# ELCD.net
KiCad netlist of a schematic drawn in Altium Designer
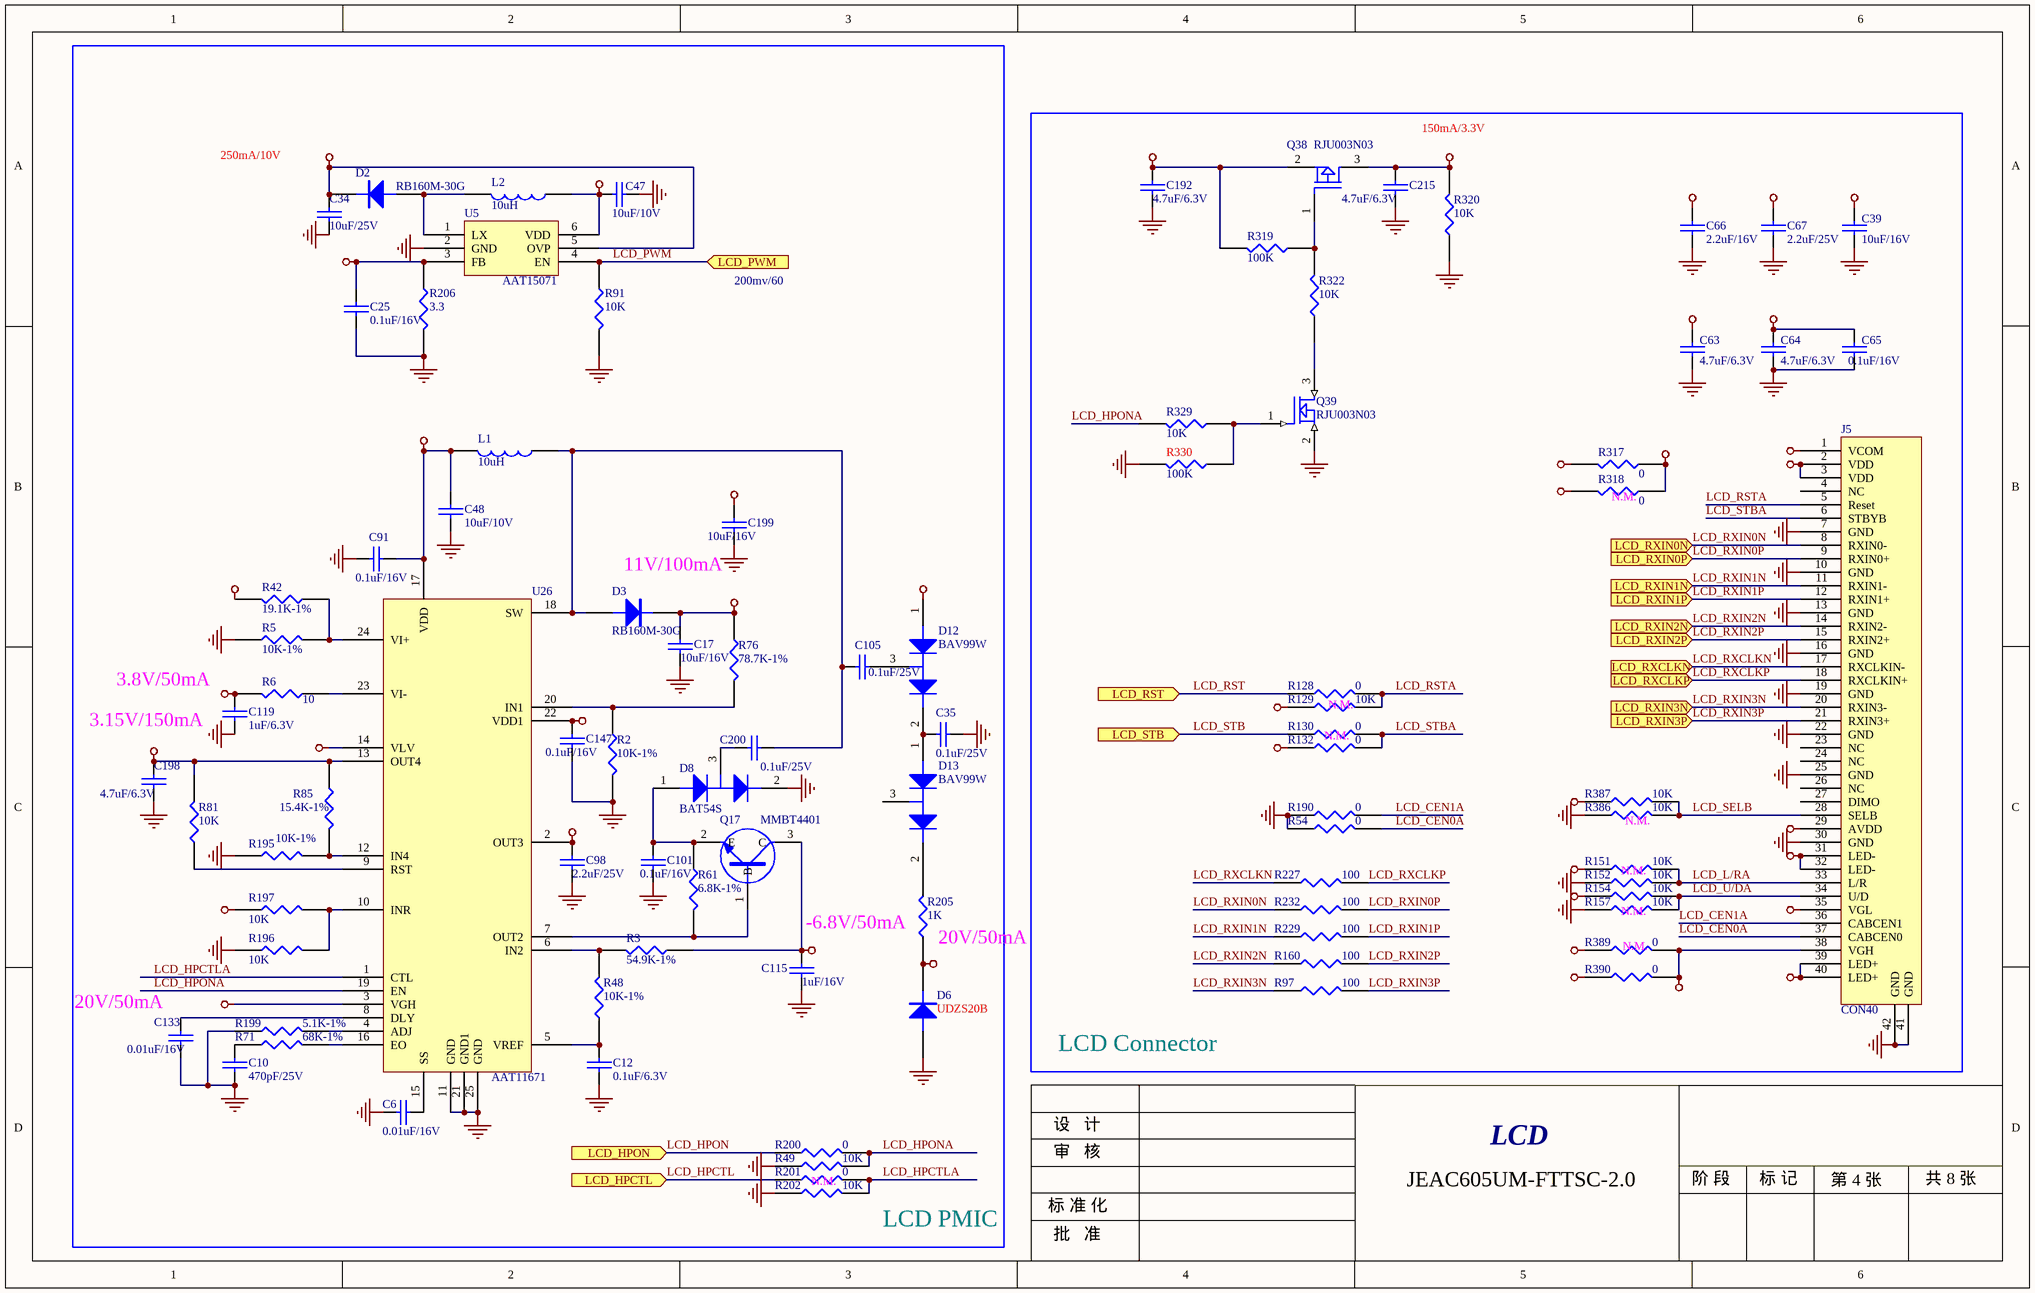
[diagram p0: ELCD.schdoc]

(export (version "E")
  (design (tool "Eeschema 10.0.6"))
  (components
    (comp (ref "C6")
      (value "0.01uF/16V")
      (footprint "C0402")
      (description "Capacitor")
      (libsource (lib "*") (part "CAP"))
    )
    (comp (ref "C10")
      (value "470pF/25V")
      (footprint "C0402")
      (description "Capacitor")
      (libsource (lib "*") (part "CAP"))
    )
    (comp (ref "C12")
      (value "0.1uF/6.3V")
      (footprint "C0402")
      (description "Capacitor")
      (libsource (lib "*") (part "CAP"))
    )
    (comp (ref "C17")
      (value "10uF/16V")
      (footprint "C1206")
      (description "Capacitor")
      (libsource (lib "*") (part "CAP"))
    )
    (comp (ref "C25")
      (value "0.1uF/16V")
      (footprint "C0402")
      (description "Capacitor")
      (libsource (lib "*") (part "CAP"))
    )
    (comp (ref "C34")
      (value "10uF/25V")
      (footprint "C1206")
      (description "Capacitor")
      (libsource (lib "*") (part "CAP"))
    )
    (comp (ref "C35")
      (value "0.1uF/25V")
      (footprint "C0603")
      (description "Capacitor")
      (libsource (lib "*") (part "CAP"))
    )
    (comp (ref "C39")
      (value "10uF/16V")
      (footprint "C1206")
      (description "Capacitor")
      (libsource (lib "*") (part "CAP"))
    )
    (comp (ref "C47")
      (value "10uF/10V")
      (footprint "C0805")
      (description "Capacitor")
      (libsource (lib "*") (part "CAP"))
    )
    (comp (ref "C48")
      (value "10uF/10V")
      (footprint "C0805")
      (description "Capacitor")
      (libsource (lib "*") (part "CAP"))
    )
    (comp (ref "C63")
      (value "4.7uF/6.3V")
      (footprint "C0603")
      (description "Capacitor")
      (libsource (lib "*") (part "CAP"))
    )
    (comp (ref "C64")
      (value "4.7uF/6.3V")
      (footprint "C0603")
      (description "Capacitor")
      (libsource (lib "*") (part "CAP"))
    )
    (comp (ref "C65")
      (value "0.1uF/16V")
      (footprint "C0402")
      (description "Capacitor")
      (libsource (lib "*") (part "CAP"))
    )
    (comp (ref "C66")
      (value "2.2uF/16V")
      (footprint "C0805")
      (description "Capacitor")
      (libsource (lib "*") (part "CAP"))
    )
    (comp (ref "C67")
      (value "2.2uF/25V")
      (footprint "C0805")
      (description "Capacitor")
      (libsource (lib "*") (part "CAP"))
    )
    (comp (ref "C91")
      (value "0.1uF/16V")
      (footprint "C0402")
      (description "Capacitor")
      (libsource (lib "*") (part "CAP"))
    )
    (comp (ref "C98")
      (value "0.1uF/16V")
      (footprint "C0805")
      (description "Capacitor")
      (libsource (lib "*") (part "CAP"))
    )
    (comp (ref "C101")
      (value "2.2uF/25V")
      (footprint "C0402")
      (description "Capacitor")
      (libsource (lib "*") (part "CAP"))
    )
    (comp (ref "C105")
      (value "0.1uF/25V")
      (footprint "C0603")
      (description "Capacitor")
      (libsource (lib "*") (part "CAP"))
    )
    (comp (ref "C115")
      (value "1uF/16V")
      (footprint "C0603")
      (description "Capacitor")
      (libsource (lib "*") (part "CAP"))
    )
    (comp (ref "C119")
      (value "1uF/6.3V")
      (footprint "C0402")
      (description "Capacitor")
      (libsource (lib "*") (part "CAP"))
    )
    (comp (ref "C133")
      (value "0.01uF/16V")
      (footprint "C0402")
      (description "Capacitor")
      (libsource (lib "*") (part "CAP"))
    )
    (comp (ref "C147")
      (value "0.1uF/16V")
      (footprint "C0402")
      (description "Capacitor")
      (libsource (lib "*") (part "CAP"))
    )
    (comp (ref "C192")
      (value "4.7uF/6.3V")
      (footprint "C0603")
      (description "Capacitor")
      (libsource (lib "*") (part "CAP"))
    )
    (comp (ref "C198")
      (value "4.7uF/6.3V")
      (footprint "C0603")
      (description "Capacitor")
      (libsource (lib "*") (part "CAP"))
    )
    (comp (ref "C199")
      (value "10uF/16V")
      (footprint "C1206")
      (description "Capacitor")
      (libsource (lib "*") (part "CAP"))
    )
    (comp (ref "C200")
      (value "0.1uF/25V")
      (footprint "C0603")
      (description "Capacitor")
      (libsource (lib "*") (part "CAP"))
    )
    (comp (ref "C215")
      (value "4.7uF/6.3V")
      (footprint "C0603")
      (description "Capacitor")
      (libsource (lib "*") (part "CAP"))
    )
    (comp (ref "D2") (value "RB160M-30G") (footprint "SOD-123") (libsource (lib "*") (part "DIODE")))
    (comp (ref "D3") (value "RB160M-30G") (footprint "SOD-123") (libsource (lib "*") (part "DIODE")))
    (comp (ref "D6") (value "UDZS20B") (footprint "UDZS24B") (libsource (lib "*") (part "DIODE")))
    (comp (ref "D8") (value "BAT54S") (footprint "SOT-23") (libsource (lib "DXP-SCHLIB") (part "MBRS1100")))
    (comp (ref "D12") (value "BAV99W") (footprint "SOT-23") (libsource (lib "") (part "MBRS1100_1")))
    (comp (ref "D13") (value "BAV99W") (footprint "SOT-23") (libsource (lib "") (part "MBRS1100_1")))
    (comp (ref "J5") (value "CON40") (footprint "j-con-40-0_5f") (libsource (lib "IMX53") (part "CON40")))
    (comp (ref "L1") (value "10uH") (footprint "l-2-EIA1008") (libsource (lib "*") (part "INDUCTOR1")))
    (comp (ref "L2") (value "10uH") (footprint "l-2-EIA1008") (libsource (lib "*") (part "INDUCTOR1")))
    (comp (ref "Q17")
      (value "MMBT4401")
      (footprint "SOT-23-NPN")
      (description "NPN Transistor")
      (libsource (lib "*") (part "NPN"))
    )
    (comp (ref "Q38") (value "RJU003N03") (footprint "SOT-23") (libsource (lib "*") (part "SI1021")))
    (comp (ref "Q39") (value "RJU003N03") (footprint "SOT-23-NPN") (libsource (lib "*") (part "MOSFET N")))
    (comp (ref "R2") (value "10K-1%") (footprint "R0402") (libsource (lib "*") (part "RES1")))
    (comp (ref "R3") (value "54.9K-1%") (footprint "R0402") (libsource (lib "*") (part "RES1")))
    (comp (ref "R5") (value "10K-1%") (footprint "R0402") (libsource (lib "*") (part "RES1")))
    (comp (ref "R6") (value "10") (footprint "R0402") (libsource (lib "*") (part "RES1")))
    (comp (ref "R42") (value "19.1K-1%") (footprint "R0402") (libsource (lib "*") (part "RES1")))
    (comp (ref "R48") (value "10K-1%") (footprint "R0402") (libsource (lib "*") (part "RES1")))
    (comp (ref "R49") (value "10K") (footprint "R0402") (libsource (lib "*") (part "RES1")))
    (comp (ref "R54") (value "0") (footprint "R0402") (libsource (lib "*") (part "RES1")))
    (comp (ref "R61") (value "6.8K-1%") (footprint "R0402") (libsource (lib "*") (part "RES1")))
    (comp (ref "R71") (value "68K-1%") (footprint "R0402") (libsource (lib "*") (part "RES1")))
    (comp (ref "R76") (value "78.7K-1%") (footprint "R0402") (libsource (lib "*") (part "RES1")))
    (comp (ref "R81") (value "10K") (footprint "R0402") (libsource (lib "*") (part "RES1")))
    (comp (ref "R85") (value "15.4K-1%") (footprint "R0402") (libsource (lib "*") (part "RES1")))
    (comp (ref "R91") (value "10K") (footprint "R0402") (libsource (lib "*") (part "RES1")))
    (comp (ref "R97") (value "100") (footprint "R0402") (libsource (lib "*") (part "RES1")))
    (comp (ref "R128") (value "0") (footprint "R0402") (libsource (lib "*") (part "RES1")))
    (comp (ref "R129") (value "10K") (footprint "R0402") (libsource (lib "*") (part "RES1")))
    (comp (ref "R130") (value "0") (footprint "R0402") (libsource (lib "*") (part "RES1")))
    (comp (ref "R132") (value "0") (footprint "R0402") (libsource (lib "*") (part "RES1")))
    (comp (ref "R151") (value "10K") (footprint "R0402") (libsource (lib "*") (part "RES1")))
    (comp (ref "R152") (value "10K") (footprint "R0402") (libsource (lib "*") (part "RES1")))
    (comp (ref "R154") (value "10K") (footprint "R0402") (libsource (lib "*") (part "RES1")))
    (comp (ref "R157") (value "10K") (footprint "R0402") (libsource (lib "*") (part "RES1")))
    (comp (ref "R160") (value "100") (footprint "R0402") (libsource (lib "*") (part "RES1")))
    (comp (ref "R190") (value "0") (footprint "R0402") (libsource (lib "*") (part "RES1")))
    (comp (ref "R195") (value "10K-1%") (footprint "R0402") (libsource (lib "*") (part "RES1")))
    (comp (ref "R196") (value "10K") (footprint "R0402") (libsource (lib "*") (part "RES1")))
    (comp (ref "R197") (value "10K") (footprint "R0402") (libsource (lib "*") (part "RES1")))
    (comp (ref "R199") (value "5.1K-1%") (footprint "R0402") (libsource (lib "*") (part "RES1")))
    (comp (ref "R200") (value "0") (footprint "R0402") (libsource (lib "*") (part "RES1")))
    (comp (ref "R201") (value "0") (footprint "R0402") (libsource (lib "*") (part "RES1")))
    (comp (ref "R202") (value "10K") (footprint "R0402") (libsource (lib "*") (part "RES1")))
    (comp (ref "R205") (value "1K") (footprint "R0603") (libsource (lib "*") (part "RES1")))
    (comp (ref "R206") (value "3.3") (footprint "R0603") (libsource (lib "*") (part "RES1")))
    (comp (ref "R227") (value "100") (footprint "R0402") (libsource (lib "*") (part "RES1")))
    (comp (ref "R229") (value "100") (footprint "R0402") (libsource (lib "*") (part "RES1")))
    (comp (ref "R232") (value "100") (footprint "R0402") (libsource (lib "*") (part "RES1")))
    (comp (ref "R317") (value "0") (footprint "R0402") (libsource (lib "*") (part "RES1")))
    (comp (ref "R318") (value "0") (footprint "R0402") (libsource (lib "*") (part "RES1")))
    (comp (ref "R319") (value "100K") (footprint "R0402") (libsource (lib "*") (part "RES1")))
    (comp (ref "R320") (value "10K") (footprint "R0402") (libsource (lib "*") (part "RES1")))
    (comp (ref "R322") (value "10K") (footprint "R0402") (libsource (lib "*") (part "RES1")))
    (comp (ref "R329") (value "10K") (footprint "R0402") (libsource (lib "*") (part "RES1")))
    (comp (ref "R330") (value "100K") (footprint "R0402") (libsource (lib "*") (part "RES1")))
    (comp (ref "R386") (value "10K") (footprint "R0402") (libsource (lib "*") (part "RES1")))
    (comp (ref "R387") (value "10K") (footprint "R0402") (libsource (lib "*") (part "RES1")))
    (comp (ref "R389") (value "0") (footprint "R0402") (libsource (lib "*") (part "RES1")))
    (comp (ref "R390") (value "0") (footprint "R0402") (libsource (lib "*") (part "RES1")))
    (comp (ref "U5") (value "AAT15071") (footprint "SOT23-6-0_95") (libsource (lib "*") (part "AAT15071")))
    (comp (ref "U26")
      (value "AAT11671")
      (footprint "U-QFN-24-0_5")
      (libsource (lib "Schlib1") (part "AAT11671"))
    )
  )
  (nets
    (net (code "1") (name "/LCD_CEN0A") (class "Default")
      (node (ref "J5") (pin "37") (pinfunction "CABCEN0_37") (pintype "passive"))
      (node (ref "R54") (pin "2") (pinfunction "2_2") (pintype "passive"))
    )
    (net (code "2") (name "/LCD_CEN1A") (class "Default")
      (node (ref "J5") (pin "36") (pinfunction "CABCEN1_36") (pintype "passive"))
      (node (ref "R190") (pin "2") (pinfunction "2_2") (pintype "passive"))
    )
    (net (code "3") (name "/LCD_HPCTL") (class "Default")
      (node (ref "R201") (pin "1") (pinfunction "1_1") (pintype "passive"))
    )
    (net (code "4") (name "/LCD_HPCTLA") (class "Default")
      (node (ref "R201") (pin "2") (pinfunction "2_2") (pintype "passive"))
      (node (ref "R202") (pin "2") (pinfunction "2_2") (pintype "passive"))
      (node (ref "U26") (pin "1") (pinfunction "CTL_1") (pintype "passive"))
    )
    (net (code "5") (name "/LCD_HPON") (class "Default")
      (node (ref "R200") (pin "1") (pinfunction "1_1") (pintype "passive"))
    )
    (net (code "6") (name "/LCD_HPONA") (class "Default")
      (node (ref "R200") (pin "2") (pinfunction "2_2") (pintype "passive"))
      (node (ref "R329") (pin "2") (pinfunction "2_2") (pintype "passive"))
      (node (ref "R49") (pin "2") (pinfunction "2_2") (pintype "passive"))
      (node (ref "U26") (pin "19") (pinfunction "EN_19") (pintype "passive"))
    )
    (net (code "7") (name "/LCD_L{slash}RA") (class "Default")
      (node (ref "J5") (pin "33") (pinfunction "L/R_33") (pintype "passive"))
      (node (ref "R151") (pin "2") (pinfunction "2_2") (pintype "passive"))
      (node (ref "R152") (pin "2") (pinfunction "2_2") (pintype "passive"))
    )
    (net (code "8") (name "/LCD_PWM") (class "Default")
      (node (ref "R91") (pin "1") (pinfunction "1_1") (pintype "passive"))
      (node (ref "U5") (pin "4") (pinfunction "EN_4") (pintype "passive"))
    )
    (net (code "9") (name "/LCD_RST") (class "Default")
      (node (ref "R128") (pin "1") (pinfunction "1_1") (pintype "passive"))
    )
    (net (code "10") (name "/LCD_RSTA") (class "Default")
      (node (ref "J5") (pin "5") (pinfunction "Reset_5") (pintype "passive"))
      (node (ref "R128") (pin "2") (pinfunction "2_2") (pintype "passive"))
      (node (ref "R129") (pin "2") (pinfunction "2_2") (pintype "passive"))
    )
    (net (code "11") (name "/LCD_RXCLKN") (class "Default")
      (node (ref "J5") (pin "17") (pinfunction "RXCLKIN-_17") (pintype "passive"))
      (node (ref "R227") (pin "1") (pinfunction "1_1") (pintype "passive"))
    )
    (net (code "12") (name "/LCD_RXCLKP") (class "Default")
      (node (ref "J5") (pin "18") (pinfunction "RXCLKIN+_18") (pintype "passive"))
      (node (ref "R227") (pin "2") (pinfunction "2_2") (pintype "passive"))
    )
    (net (code "13") (name "/LCD_RXIN0N") (class "Default")
      (node (ref "J5") (pin "8") (pinfunction "RXIN0-_8") (pintype "passive"))
      (node (ref "R232") (pin "1") (pinfunction "1_1") (pintype "passive"))
    )
    (net (code "14") (name "/LCD_RXIN0P") (class "Default")
      (node (ref "J5") (pin "9") (pinfunction "RXIN0+_9") (pintype "passive"))
      (node (ref "R232") (pin "2") (pinfunction "2_2") (pintype "passive"))
    )
    (net (code "15") (name "/LCD_RXIN1N") (class "Default")
      (node (ref "J5") (pin "11") (pinfunction "RXIN1-_11") (pintype "passive"))
      (node (ref "R229") (pin "1") (pinfunction "1_1") (pintype "passive"))
    )
    (net (code "16") (name "/LCD_RXIN1P") (class "Default")
      (node (ref "J5") (pin "12") (pinfunction "RXIN1+_12") (pintype "passive"))
      (node (ref "R229") (pin "2") (pinfunction "2_2") (pintype "passive"))
    )
    (net (code "17") (name "/LCD_RXIN2N") (class "Default")
      (node (ref "J5") (pin "14") (pinfunction "RXIN2-_14") (pintype "passive"))
      (node (ref "R160") (pin "1") (pinfunction "1_1") (pintype "passive"))
    )
    (net (code "18") (name "/LCD_RXIN2P") (class "Default")
      (node (ref "J5") (pin "15") (pinfunction "RXIN2+_15") (pintype "passive"))
      (node (ref "R160") (pin "2") (pinfunction "2_2") (pintype "passive"))
    )
    (net (code "19") (name "/LCD_RXIN3N") (class "Default")
      (node (ref "J5") (pin "20") (pinfunction "RXIN3-_20") (pintype "passive"))
      (node (ref "R97") (pin "1") (pinfunction "1_1") (pintype "passive"))
    )
    (net (code "20") (name "/LCD_RXIN3P") (class "Default")
      (node (ref "J5") (pin "21") (pinfunction "RXIN3+_21") (pintype "passive"))
      (node (ref "R97") (pin "2") (pinfunction "2_2") (pintype "passive"))
    )
    (net (code "21") (name "/LCD_SELB") (class "Default")
      (node (ref "J5") (pin "28") (pinfunction "SELB_28") (pintype "passive"))
      (node (ref "R386") (pin "2") (pinfunction "2_2") (pintype "passive"))
      (node (ref "R387") (pin "2") (pinfunction "2_2") (pintype "passive"))
    )
    (net (code "22") (name "/LCD_STB") (class "Default")
      (node (ref "R130") (pin "1") (pinfunction "1_1") (pintype "passive"))
    )
    (net (code "23") (name "/LCD_STBA") (class "Default")
      (node (ref "J5") (pin "6") (pinfunction "STBYB_6") (pintype "passive"))
      (node (ref "R130") (pin "2") (pinfunction "2_2") (pintype "passive"))
      (node (ref "R132") (pin "2") (pinfunction "2_2") (pintype "passive"))
    )
    (net (code "24") (name "/LCD_U{slash}DA") (class "Default")
      (node (ref "J5") (pin "34") (pinfunction "U/D_34") (pintype "passive"))
      (node (ref "R154") (pin "2") (pinfunction "2_2") (pintype "passive"))
      (node (ref "R157") (pin "2") (pinfunction "2_2") (pintype "passive"))
    )
    (net (code "25") (name "BLED_N") (class "Default")
      (node (ref "C25") (pin "1") (pinfunction "1_1") (pintype "passive"))
      (node (ref "J5") (pin "31") (pinfunction "LED-_31") (pintype "passive"))
      (node (ref "J5") (pin "32") (pinfunction "LED-_32") (pintype "passive"))
      (node (ref "R206") (pin "1") (pinfunction "1_1") (pintype "passive"))
      (node (ref "U5") (pin "3") (pinfunction "FB_3") (pintype "passive"))
    )
    (net (code "26") (name "BLED_P") (class "Default")
      (node (ref "C34") (pin "2") (pinfunction "2_2") (pintype "passive"))
      (node (ref "D2") (pin "2") (pinfunction "2_2") (pintype "passive"))
      (node (ref "J5") (pin "39") (pinfunction "LED+_39") (pintype "passive"))
      (node (ref "J5") (pin "40") (pinfunction "LED+_40") (pintype "passive"))
      (node (ref "U5") (pin "5") (pinfunction "OVP_5") (pintype "passive"))
    )
    (net (code "27") (name "GND") (class "Default")
      (node (ref "C10") (pin "1") (pinfunction "1_1") (pintype "passive"))
      (node (ref "C101") (pin "2") (pinfunction "2_2") (pintype "passive"))
      (node (ref "C115") (pin "1") (pinfunction "1_1") (pintype "passive"))
      (node (ref "C119") (pin "1") (pinfunction "1_1") (pintype "passive"))
      (node (ref "C12") (pin "2") (pinfunction "2_2") (pintype "passive"))
      (node (ref "C133") (pin "2") (pinfunction "2_2") (pintype "passive"))
      (node (ref "C147") (pin "2") (pinfunction "2_2") (pintype "passive"))
      (node (ref "C17") (pin "1") (pinfunction "1_1") (pintype "passive"))
      (node (ref "C192") (pin "2") (pinfunction "2_2") (pintype "passive"))
      (node (ref "C198") (pin "2") (pinfunction "2_2") (pintype "passive"))
      (node (ref "C199") (pin "1") (pinfunction "1_1") (pintype "passive"))
      (node (ref "C215") (pin "1") (pinfunction "1_1") (pintype "passive"))
      (node (ref "C25") (pin "2") (pinfunction "2_2") (pintype "passive"))
      (node (ref "C34") (pin "1") (pinfunction "1_1") (pintype "passive"))
      (node (ref "C35") (pin "2") (pinfunction "2_2") (pintype "passive"))
      (node (ref "C39") (pin "2") (pinfunction "2_2") (pintype "passive"))
      (node (ref "C47") (pin "2") (pinfunction "2_2") (pintype "passive"))
      (node (ref "C48") (pin "1") (pinfunction "1_1") (pintype "passive"))
      (node (ref "C6") (pin "2") (pinfunction "2_2") (pintype "passive"))
      (node (ref "C63") (pin "2") (pinfunction "2_2") (pintype "passive"))
      (node (ref "C64") (pin "2") (pinfunction "2_2") (pintype "passive"))
      (node (ref "C65") (pin "2") (pinfunction "2_2") (pintype "passive"))
      (node (ref "C66") (pin "1") (pinfunction "1_1") (pintype "passive"))
      (node (ref "C67") (pin "1") (pinfunction "1_1") (pintype "passive"))
      (node (ref "C91") (pin "2") (pinfunction "2_2") (pintype "passive"))
      (node (ref "C98") (pin "1") (pinfunction "1_1") (pintype "passive"))
      (node (ref "D6") (pin "1") (pinfunction "1_1") (pintype "passive"))
      (node (ref "D8") (pin "2") (pinfunction "2_2") (pintype "passive"))
      (node (ref "J5") (pin "10") (pinfunction "GND_10") (pintype "passive"))
      (node (ref "J5") (pin "13") (pinfunction "GND_13") (pintype "passive"))
      (node (ref "J5") (pin "16") (pinfunction "GND_16") (pintype "passive"))
      (node (ref "J5") (pin "19") (pinfunction "GND_19") (pintype "passive"))
      (node (ref "J5") (pin "22") (pinfunction "GND_22") (pintype "passive"))
      (node (ref "J5") (pin "25") (pinfunction "GND_25") (pintype "passive"))
      (node (ref "J5") (pin "30") (pinfunction "GND_30") (pintype "passive"))
      (node (ref "J5") (pin "41") (pinfunction "GND_41") (pintype "passive"))
      (node (ref "J5") (pin "42") (pinfunction "GND_42") (pintype "passive"))
      (node (ref "J5") (pin "7") (pinfunction "GND_7") (pintype "passive"))
      (node (ref "Q39") (pin "2") (pinfunction "S_2") (pintype "input"))
      (node (ref "R152") (pin "1") (pinfunction "1_1") (pintype "passive"))
      (node (ref "R157") (pin "1") (pinfunction "1_1") (pintype "passive"))
      (node (ref "R190") (pin "1") (pinfunction "1_1") (pintype "passive"))
      (node (ref "R195") (pin "1") (pinfunction "1_1") (pintype "passive"))
      (node (ref "R196") (pin "1") (pinfunction "1_1") (pintype "passive"))
      (node (ref "R199") (pin "1") (pinfunction "1_1") (pintype "passive"))
      (node (ref "R2") (pin "2") (pinfunction "2_2") (pintype "passive"))
      (node (ref "R202") (pin "1") (pinfunction "1_1") (pintype "passive"))
      (node (ref "R206") (pin "2") (pinfunction "2_2") (pintype "passive"))
      (node (ref "R320") (pin "1") (pinfunction "1_1") (pintype "passive"))
      (node (ref "R330") (pin "2") (pinfunction "2_2") (pintype "passive"))
      (node (ref "R386") (pin "1") (pinfunction "1_1") (pintype "passive"))
      (node (ref "R49") (pin "1") (pinfunction "1_1") (pintype "passive"))
      (node (ref "R5") (pin "1") (pinfunction "1_1") (pintype "passive"))
      (node (ref "R54") (pin "1") (pinfunction "1_1") (pintype "passive"))
      (node (ref "R91") (pin "2") (pinfunction "2_2") (pintype "passive"))
      (node (ref "U26") (pin "11") (pinfunction "GND_11") (pintype "passive"))
      (node (ref "U26") (pin "21") (pinfunction "GND1_21") (pintype "passive"))
      (node (ref "U26") (pin "25") (pinfunction "GND_25") (pintype "passive"))
      (node (ref "U5") (pin "2") (pinfunction "GND_2") (pintype "passive"))
    )
    (net (code "28") (name "LCD_AVDD") (class "Default")
      (node (ref "C147") (pin "1") (pinfunction "1_1") (pintype "passive"))
      (node (ref "C17") (pin "2") (pinfunction "2_2") (pintype "passive"))
      (node (ref "C199") (pin "2") (pinfunction "2_2") (pintype "passive"))
      (node (ref "C39") (pin "1") (pinfunction "1_1") (pintype "passive"))
      (node (ref "D12") (pin "1") (pinfunction "1_1") (pintype "passive"))
      (node (ref "D3") (pin "2") (pinfunction "2_2") (pintype "passive"))
      (node (ref "J5") (pin "29") (pinfunction "AVDD_29") (pintype "passive"))
      (node (ref "R42") (pin "2") (pinfunction "2_2") (pintype "passive"))
      (node (ref "R76") (pin "1") (pinfunction "1_1") (pintype "passive"))
      (node (ref "U26") (pin "22") (pinfunction "VDD1_22") (pintype "passive"))
    )
    (net (code "29") (name "LCD_VCOM") (class "Default")
      (node (ref "C119") (pin "2") (pinfunction "2_2") (pintype "passive"))
      (node (ref "C63") (pin "1") (pinfunction "1_1") (pintype "passive"))
      (node (ref "J5") (pin "1") (pinfunction "VCOM_1") (pintype "passive"))
      (node (ref "R6") (pin "2") (pinfunction "2_2") (pintype "passive"))
    )
    (net (code "30") (name "LCD_VGH") (class "Default")
      (node (ref "C67") (pin "2") (pinfunction "2_2") (pintype "passive"))
      (node (ref "J5") (pin "38") (pinfunction "VGH_38") (pintype "passive"))
      (node (ref "R389") (pin "2") (pinfunction "2_2") (pintype "passive"))
      (node (ref "R390") (pin "2") (pinfunction "2_2") (pintype "passive"))
    )
    (net (code "31") (name "LCD_VGL") (class "Default")
      (node (ref "C115") (pin "2") (pinfunction "2_2") (pintype "passive"))
      (node (ref "C66") (pin "2") (pinfunction "2_2") (pintype "passive"))
      (node (ref "J5") (pin "35") (pinfunction "VGL_35") (pintype "passive"))
      (node (ref "Q17") (pin "3") (pinfunction "C_3") (pintype "passive"))
      (node (ref "R3") (pin "1") (pinfunction "1_1") (pintype "passive"))
    )
    (net (code "32") (name "Net-(C10-Pad2)") (class "Default")
      (node (ref "C10") (pin "2") (pinfunction "2_2") (pintype "passive"))
      (node (ref "R71") (pin "1") (pinfunction "1_1") (pintype "passive"))
    )
    (net (code "33") (name "Net-(C35-Pad1)") (class "Default")
      (node (ref "C35") (pin "1") (pinfunction "1_1") (pintype "passive"))
      (node (ref "D12") (pin "2") (pinfunction "2_2") (pintype "passive"))
      (node (ref "D13") (pin "1") (pinfunction "1_1") (pintype "passive"))
    )
    (net (code "34") (name "Net-(C105-Pad2)") (class "Default")
      (node (ref "C105") (pin "2") (pinfunction "2_2") (pintype "passive"))
      (node (ref "D12") (pin "3") (pinfunction "3_3") (pintype "passive"))
    )
    (net (code "35") (name "Net-(C200-Pad1)") (class "Default")
      (node (ref "C200") (pin "1") (pinfunction "1_1") (pintype "passive"))
      (node (ref "D8") (pin "3") (pinfunction "3_3") (pintype "passive"))
    )
    (net (code "36") (name "Net-(D13-Pad2)") (class "Default")
      (node (ref "D13") (pin "2") (pinfunction "2_2") (pintype "passive"))
      (node (ref "R205") (pin "2") (pinfunction "2_2") (pintype "passive"))
    )
    (net (code "37") (name "Net-(Q17-B)") (class "Default")
      (node (ref "Q17") (pin "1") (pinfunction "B_1") (pintype "passive"))
      (node (ref "R61") (pin "2") (pinfunction "2_2") (pintype "passive"))
      (node (ref "U26") (pin "7") (pinfunction "OUT2_7") (pintype "passive"))
    )
    (net (code "38") (name "Net-(Q17-E)") (class "Default")
      (node (ref "C101") (pin "1") (pinfunction "1_1") (pintype "passive"))
      (node (ref "D8") (pin "1") (pinfunction "1_1") (pintype "passive"))
      (node (ref "Q17") (pin "2") (pinfunction "E_2") (pintype "passive"))
      (node (ref "R61") (pin "1") (pinfunction "1_1") (pintype "passive"))
    )
    (net (code "39") (name "Net-(Q38-G)") (class "Default")
      (node (ref "Q38") (pin "1") (pinfunction "G_1") (pintype "passive"))
      (node (ref "R319") (pin "1") (pinfunction "1_1") (pintype "passive"))
      (node (ref "R322") (pin "2") (pinfunction "2_2") (pintype "passive"))
    )
    (net (code "40") (name "Net-(Q39-D)") (class "Default")
      (node (ref "Q39") (pin "3") (pinfunction "D_3") (pintype "input"))
      (node (ref "R322") (pin "1") (pinfunction "1_1") (pintype "passive"))
    )
    (net (code "41") (name "Net-(Q39-G)") (class "Default")
      (node (ref "Q39") (pin "1") (pinfunction "G_1") (pintype "input"))
      (node (ref "R329") (pin "1") (pinfunction "1_1") (pintype "passive"))
      (node (ref "R330") (pin "1") (pinfunction "1_1") (pintype "passive"))
    )
    (net (code "42") (name "Net-(U5-LX)") (class "Default")
      (node (ref "D2") (pin "1") (pinfunction "1_1") (pintype "passive"))
      (node (ref "L2") (pin "2") (pinfunction "2_2") (pintype "passive"))
      (node (ref "U5") (pin "1") (pinfunction "LX_1") (pintype "passive"))
    )
    (net (code "43") (name "Net-(U26-ADJ)") (class "Default")
      (node (ref "R199") (pin "2") (pinfunction "2_2") (pintype "passive"))
      (node (ref "U26") (pin "4") (pinfunction "ADJ_4") (pintype "passive"))
    )
    (net (code "44") (name "Net-(U26-DLY)") (class "Default")
      (node (ref "C133") (pin "1") (pinfunction "1_1") (pintype "passive"))
      (node (ref "U26") (pin "8") (pinfunction "DLY_8") (pintype "passive"))
    )
    (net (code "45") (name "Net-(U26-EO)") (class "Default")
      (node (ref "R71") (pin "2") (pinfunction "2_2") (pintype "passive"))
      (node (ref "U26") (pin "16") (pinfunction "EO_16") (pintype "passive"))
    )
    (net (code "46") (name "Net-(U26-IN1)") (class "Default")
      (node (ref "R2") (pin "1") (pinfunction "1_1") (pintype "passive"))
      (node (ref "R76") (pin "2") (pinfunction "2_2") (pintype "passive"))
      (node (ref "U26") (pin "20") (pinfunction "IN1_20") (pintype "passive"))
    )
    (net (code "47") (name "Net-(U26-IN2)") (class "Default")
      (node (ref "R3") (pin "2") (pinfunction "2_2") (pintype "passive"))
      (node (ref "R48") (pin "2") (pinfunction "2_2") (pintype "passive"))
      (node (ref "U26") (pin "6") (pinfunction "IN2_6") (pintype "passive"))
    )
    (net (code "48") (name "Net-(U26-IN4)") (class "Default")
      (node (ref "R195") (pin "2") (pinfunction "2_2") (pintype "passive"))
      (node (ref "R85") (pin "2") (pinfunction "2_2") (pintype "passive"))
      (node (ref "U26") (pin "12") (pinfunction "IN4_12") (pintype "passive"))
    )
    (net (code "49") (name "Net-(U26-INR)") (class "Default")
      (node (ref "R196") (pin "2") (pinfunction "2_2") (pintype "passive"))
      (node (ref "R197") (pin "2") (pinfunction "2_2") (pintype "passive"))
      (node (ref "U26") (pin "10") (pinfunction "INR_10") (pintype "passive"))
    )
    (net (code "50") (name "Net-(U26-RST)") (class "Default")
      (node (ref "R81") (pin "1") (pinfunction "1_1") (pintype "passive"))
      (node (ref "U26") (pin "9") (pinfunction "RST_9") (pintype "passive"))
    )
    (net (code "51") (name "Net-(U26-SS)") (class "Default")
      (node (ref "C6") (pin "1") (pinfunction "1_1") (pintype "passive"))
      (node (ref "U26") (pin "15") (pinfunction "SS_15") (pintype "passive"))
    )
    (net (code "52") (name "Net-(U26-SW)") (class "Default")
      (node (ref "C105") (pin "1") (pinfunction "1_1") (pintype "passive"))
      (node (ref "C200") (pin "2") (pinfunction "2_2") (pintype "passive"))
      (node (ref "D3") (pin "1") (pinfunction "1_1") (pintype "passive"))
      (node (ref "L1") (pin "1") (pinfunction "1_1") (pintype "passive"))
      (node (ref "U26") (pin "18") (pinfunction "SW_18") (pintype "passive"))
    )
    (net (code "53") (name "Net-(U26-VI+)") (class "Default")
      (node (ref "R42") (pin "1") (pinfunction "1_1") (pintype "passive"))
      (node (ref "R5") (pin "2") (pinfunction "2_2") (pintype "passive"))
      (node (ref "U26") (pin "24") (pinfunction "VI+_24") (pintype "passive"))
    )
    (net (code "54") (name "Net-(U26-VI-)") (class "Default")
      (node (ref "R6") (pin "1") (pinfunction "1_1") (pintype "passive"))
      (node (ref "U26") (pin "23") (pinfunction "VI-_23") (pintype "passive"))
    )
    (net (code "55") (name "Net-(U26-VREF)") (class "Default")
      (node (ref "C12") (pin "1") (pinfunction "1_1") (pintype "passive"))
      (node (ref "R48") (pin "1") (pinfunction "1_1") (pintype "passive"))
      (node (ref "U26") (pin "5") (pinfunction "VREF_5") (pintype "passive"))
    )
    (net (code "56") (name "VCC_3V") (class "Default")
      (node (ref "C192") (pin "1") (pinfunction "1_1") (pintype "passive"))
      (node (ref "Q38") (pin "2") (pinfunction "S_2") (pintype "passive"))
      (node (ref "R319") (pin "2") (pinfunction "2_2") (pintype "passive"))
    )
    (net (code "57") (name "VCC_LCD") (class "Default")
      (node (ref "C64") (pin "1") (pinfunction "1_1") (pintype "passive"))
      (node (ref "C65") (pin "1") (pinfunction "1_1") (pintype "passive"))
      (node (ref "J5") (pin "2") (pinfunction "VDD_2") (pintype "passive"))
      (node (ref "J5") (pin "3") (pinfunction "VDD_3") (pintype "passive"))
      (node (ref "R129") (pin "1") (pinfunction "1_1") (pintype "passive"))
      (node (ref "R132") (pin "1") (pinfunction "1_1") (pintype "passive"))
      (node (ref "R151") (pin "1") (pinfunction "1_1") (pintype "passive"))
      (node (ref "R154") (pin "1") (pinfunction "1_1") (pintype "passive"))
      (node (ref "R317") (pin "1") (pinfunction "1_1") (pintype "passive"))
      (node (ref "R318") (pin "1") (pinfunction "1_1") (pintype "passive"))
      (node (ref "R387") (pin "1") (pinfunction "1_1") (pintype "passive"))
    )
    (net (code "58") (name "VCC_LCD1") (class "Default")
      (node (ref "C198") (pin "1") (pinfunction "1_1") (pintype "passive"))
      (node (ref "R197") (pin "1") (pinfunction "1_1") (pintype "passive"))
      (node (ref "R318") (pin "2") (pinfunction "2_2") (pintype "passive"))
      (node (ref "R81") (pin "2") (pinfunction "2_2") (pintype "passive"))
      (node (ref "R85") (pin "1") (pinfunction "1_1") (pintype "passive"))
      (node (ref "U26") (pin "13") (pinfunction "OUT4_13") (pintype "passive"))
    )
    (net (code "59") (name "VCC_LCD2") (class "Default")
      (node (ref "C215") (pin "2") (pinfunction "2_2") (pintype "passive"))
      (node (ref "Q38") (pin "3") (pinfunction "D_3") (pintype "passive"))
      (node (ref "R317") (pin "2") (pinfunction "2_2") (pintype "passive"))
      (node (ref "R320") (pin "2") (pinfunction "2_2") (pintype "passive"))
    )
    (net (code "60") (name "VDD_VGH") (class "Default")
      (node (ref "R390") (pin "1") (pinfunction "1_1") (pintype "passive"))
      (node (ref "U26") (pin "3") (pinfunction "VGH_3") (pintype "passive"))
    )
    (net (code "61") (name "VOUT3") (class "Default")
      (node (ref "C98") (pin "2") (pinfunction "2_2") (pintype "passive"))
      (node (ref "D6") (pin "2") (pinfunction "2_2") (pintype "passive"))
      (node (ref "R205") (pin "1") (pinfunction "1_1") (pintype "passive"))
      (node (ref "R389") (pin "1") (pinfunction "1_1") (pintype "passive"))
      (node (ref "U26") (pin "2") (pinfunction "OUT3_2") (pintype "passive"))
    )
    (net (code "62") (name "V_HS") (class "Default")
      (node (ref "C47") (pin "1") (pinfunction "1_1") (pintype "passive"))
      (node (ref "C48") (pin "2") (pinfunction "2_2") (pintype "passive"))
      (node (ref "C91") (pin "1") (pinfunction "1_1") (pintype "passive"))
      (node (ref "L1") (pin "2") (pinfunction "2_2") (pintype "passive"))
      (node (ref "L2") (pin "1") (pinfunction "1_1") (pintype "passive"))
      (node (ref "U26") (pin "14") (pinfunction "VLV_14") (pintype "passive"))
      (node (ref "U26") (pin "17") (pinfunction "VDD_17") (pintype "passive"))
      (node (ref "U5") (pin "6") (pinfunction "VDD_6") (pintype "passive"))
    )
    (net (code "63") (name "unconnected-(D13-Pad3)") (class "Default")
      (node (ref "D13") (pin "3") (pinfunction "3_3") (pintype "passive"))
    )
    (net (code "64") (name "unconnected-(J5-DIMO-Pad27)") (class "Default")
      (node (ref "J5") (pin "27") (pinfunction "DIMO_27") (pintype "passive"))
    )
    (net (code "65") (name "unconnected-(J5-NC-Pad4)") (class "Default")
      (node (ref "J5") (pin "4") (pinfunction "NC_4") (pintype "passive"))
    )
    (net (code "66") (name "unconnected-(J5-NC-Pad23)") (class "Default")
      (node (ref "J5") (pin "23") (pinfunction "NC_23") (pintype "passive"))
    )
    (net (code "67") (name "unconnected-(J5-NC-Pad24)") (class "Default")
      (node (ref "J5") (pin "24") (pinfunction "NC_24") (pintype "passive"))
    )
    (net (code "68") (name "unconnected-(J5-NC-Pad26)") (class "Default")
      (node (ref "J5") (pin "26") (pinfunction "NC_26") (pintype "passive"))
    )
  )
)
